# beefocus.net
KiCad netlist of a schematic drawn in EAGLE
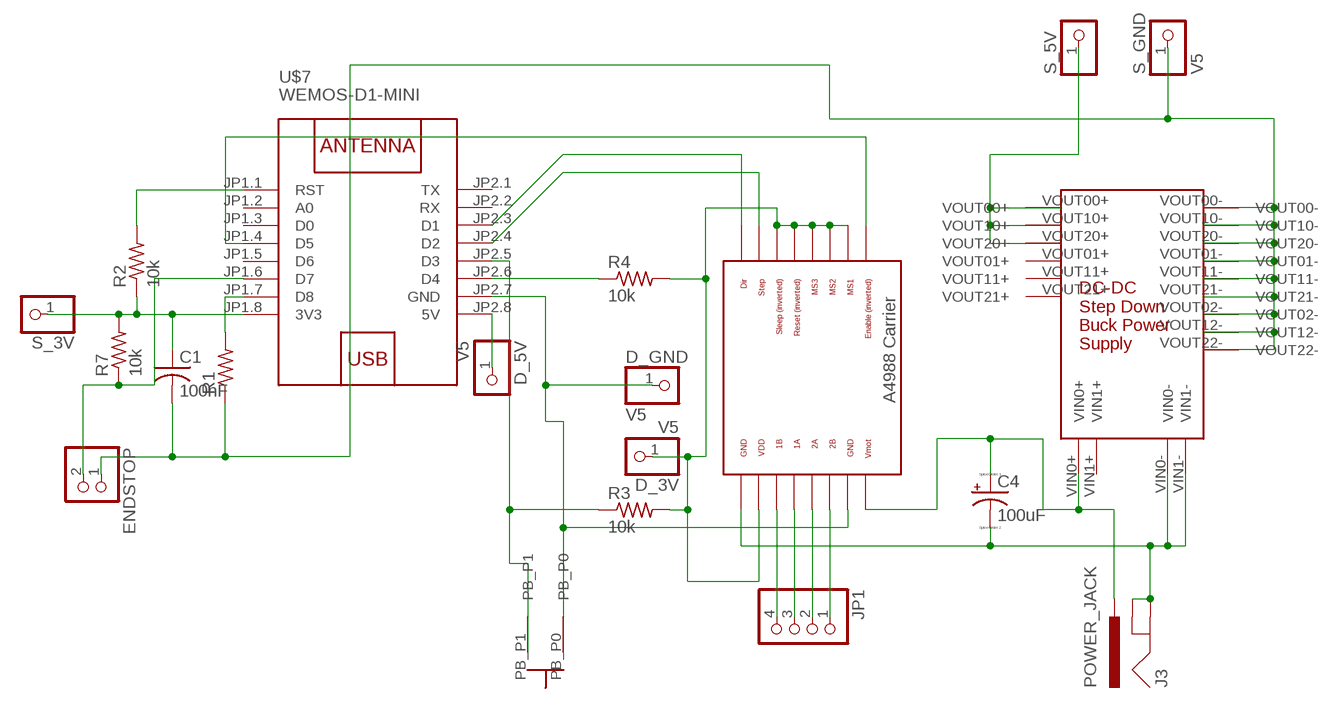
[diagram p0: schematic, sheet 1]

(export (version "E")
  (design (tool "Eeschema 10.0.6"))
  (components
    (comp (ref "C1")
      (value "100nF")
      (footprint "eagle-import:C050-024X044")
      (libsource (lib "eagle-import") (part "C-US050-024X044"))
    )
    (comp (ref "C4")
      (value "100uF")
      (footprint "eagle-import:E3,5-8")
      (libsource (lib "eagle-import") (part "CPOL-USE3.5-8"))
    )
    (comp (ref "D_3V")
      (value "V5")
      (footprint "eagle-import:1X01")
      (libsource (lib "eagle-import") (part "PINHD-1X1"))
    )
    (comp (ref "D_5V")
      (value "V5")
      (footprint "eagle-import:1X01")
      (libsource (lib "eagle-import") (part "PINHD-1X1"))
    )
    (comp (ref "D_GND")
      (value "V5")
      (footprint "eagle-import:1X01")
      (libsource (lib "eagle-import") (part "PINHD-1X1"))
    )
    (comp (ref "ENDSTOP")
      (value "PINHD-1X2/90")
      (footprint "eagle-import:1X02_90")
      (libsource (lib "eagle-import") (part "PINHD-1X2/90"))
    )
    (comp (ref "J3")
      (value "POWER_JACK")
      (footprint "eagle-import:POWER_JACK_PTH")
      (libsource (lib "eagle-import") (part "POWER_JACK"))
    )
    (comp (ref "JP1")
      (value "PINHD-1X4/90")
      (footprint "eagle-import:1X04_90")
      (libsource (lib "eagle-import") (part "PINHD-1X4/90"))
    )
    (comp (ref "R1")
      (value "R-US_0204/7")
      (footprint "eagle-import:0204_7")
      (libsource (lib "eagle-import") (part "R-US_0204/7"))
    )
    (comp (ref "R2")
      (value "10k")
      (footprint "eagle-import:0204_7")
      (libsource (lib "eagle-import") (part "R-US_0204/7"))
    )
    (comp (ref "R3")
      (value "10k")
      (footprint "eagle-import:0309V")
      (libsource (lib "eagle-import") (part "R-US_0309/V"))
    )
    (comp (ref "R4")
      (value "10k")
      (footprint "eagle-import:0204_7")
      (libsource (lib "eagle-import") (part "R-US_0204/7"))
    )
    (comp (ref "R7")
      (value "10k")
      (footprint "eagle-import:0309V")
      (libsource (lib "eagle-import") (part "R-US_0309/V"))
    )
    (comp (ref "S_3V")
      (value "PINHD-1X1")
      (footprint "eagle-import:1X01")
      (libsource (lib "eagle-import") (part "PINHD-1X1"))
    )
    (comp (ref "S_5V")
      (value "PINHD-1X1")
      (footprint "eagle-import:1X01")
      (libsource (lib "eagle-import") (part "PINHD-1X1"))
    )
    (comp (ref "S_GND")
      (value "V5")
      (footprint "eagle-import:1X01")
      (libsource (lib "eagle-import") (part "PINHD-1X1"))
    )
    (comp (ref "U$1")
      (value "POLOLU_A4983CARRIER")
      (footprint "eagle-import:A4988BREAKOUT")
      (libsource (lib "eagle-import") (part "POLOLU_A4983CARRIER"))
    )
    (comp (ref "U$6")
      (value "DCPOWERCONV_R2")
      (footprint "eagle-import:DCPOWERCONV_R2")
      (libsource (lib "eagle-import") (part "DCPOWERCONV_R2"))
    )
    (comp (ref "U$7")
      (value "WEMOS-D1-MINI")
      (footprint "eagle-import:WEMOS-D1-MINI")
      (libsource (lib "eagle-import") (part "WEMOS-D1-MINI"))
    )
    (comp (ref "U$8")
      (value "BUTTON6X6X10MMSIDE")
      (footprint "eagle-import:BUTTON6X6X10MMSIDE")
      (libsource (lib "eagle-import") (part "BUTTON6X6X10MMSIDE"))
    )
  )
  (nets
    (net (code "1") (name "Net-(C1-Pad2)") (class "Default")
      (node (ref "C1") (pin "2") (pinfunction "2_2") (pintype "passive"))
      (node (ref "ENDSTOP") (pin "1") (pinfunction "1_1") (pintype "passive"))
      (node (ref "R1") (pin "1") (pinfunction "1_1") (pintype "passive"))
      (node (ref "S_GND") (pin "1") (pinfunction "1_1") (pintype "passive"))
      (node (ref "U$6") (pin "VOUT00-") (pinfunction "VOUT00-_VOUT00-") (pintype "bidirectional"))
      (node (ref "U$6") (pin "VOUT01-") (pinfunction "VOUT01-_VOUT01-") (pintype "bidirectional"))
      (node (ref "U$6") (pin "VOUT02-") (pinfunction "VOUT02-_VOUT02-") (pintype "bidirectional"))
      (node (ref "U$6") (pin "VOUT10-") (pinfunction "VOUT10-_VOUT10-") (pintype "bidirectional"))
      (node (ref "U$6") (pin "VOUT11-") (pinfunction "VOUT11-_VOUT11-") (pintype "bidirectional"))
      (node (ref "U$6") (pin "VOUT12-") (pinfunction "VOUT12-_VOUT12-") (pintype "bidirectional"))
      (node (ref "U$6") (pin "VOUT20-") (pinfunction "VOUT20-_VOUT20-") (pintype "bidirectional"))
      (node (ref "U$6") (pin "VOUT21-") (pinfunction "VOUT21-_VOUT21-") (pintype "bidirectional"))
      (node (ref "U$6") (pin "VOUT22-") (pinfunction "VOUT22-_VOUT22-") (pintype "bidirectional"))
    )
    (net (code "2") (name "Net-(C4-Pad+)") (class "Default")
      (node (ref "C4") (pin "+") (pinfunction "+_+") (pintype "passive"))
      (node (ref "J3") (pin "PWR") (pinfunction "PWR_PWR") (pintype "bidirectional"))
      (node (ref "U$1") (pin "VMOT") (pinfunction "VMOT_VMOT") (pintype "power_in"))
      (node (ref "U$6") (pin "VIN0+") (pinfunction "VIN0+_VIN0+") (pintype "bidirectional"))
    )
    (net (code "3") (name "Net-(C4-Pad-)") (class "Default")
      (node (ref "C4") (pin "-") (pinfunction "-_-") (pintype "passive"))
      (node (ref "J3") (pin "GND") (pinfunction "GND_GND") (pintype "bidirectional"))
      (node (ref "J3") (pin "GNDBREAK") (pinfunction "GNDBREAK_GNDBREAK") (pintype "bidirectional"))
      (node (ref "U$1") (pin "GND@0") (pinfunction "GND_GND@0") (pintype "power_in"))
      (node (ref "U$6") (pin "VIN0-") (pinfunction "VIN0-_VIN0-") (pintype "bidirectional"))
      (node (ref "U$6") (pin "VIN1-") (pinfunction "VIN1-_VIN1-") (pintype "bidirectional"))
    )
    (net (code "4") (name "Net-(JP1-Pad1)") (class "Default")
      (node (ref "JP1") (pin "1") (pinfunction "1_1") (pintype "passive"))
      (node (ref "U$1") (pin "2B") (pinfunction "2B_2B") (pintype "output"))
    )
    (net (code "5") (name "Net-(JP1-Pad2)") (class "Default")
      (node (ref "JP1") (pin "2") (pinfunction "2_2") (pintype "passive"))
      (node (ref "U$1") (pin "2A") (pinfunction "2A_2A") (pintype "output"))
    )
    (net (code "6") (name "Net-(JP1-Pad3)") (class "Default")
      (node (ref "JP1") (pin "3") (pinfunction "3_3") (pintype "passive"))
      (node (ref "U$1") (pin "1A") (pinfunction "1A_1A") (pintype "output"))
    )
    (net (code "7") (name "Net-(JP1-Pad4)") (class "Default")
      (node (ref "JP1") (pin "4") (pinfunction "4_4") (pintype "passive"))
      (node (ref "U$1") (pin "1B") (pinfunction "1B_1B") (pintype "output"))
    )
    (net (code "8") (name "Net-(S_5V-Pad1)") (class "Default")
      (node (ref "S_5V") (pin "1") (pinfunction "1_1") (pintype "passive"))
      (node (ref "U$6") (pin "VOUT00+") (pinfunction "VOUT00+_VOUT00+") (pintype "bidirectional"))
      (node (ref "U$6") (pin "VOUT10+") (pinfunction "VOUT10+_VOUT10+") (pintype "bidirectional"))
      (node (ref "U$6") (pin "VOUT20+") (pinfunction "VOUT20+_VOUT20+") (pintype "bidirectional"))
    )
    (net (code "9") (name "Net-(U$1-SLEEP)") (class "Default")
      (node (ref "D_3V") (pin "1") (pinfunction "1_1") (pintype "passive"))
      (node (ref "R3") (pin "2") (pinfunction "2_2") (pintype "passive"))
      (node (ref "R4") (pin "2") (pinfunction "2_2") (pintype "passive"))
      (node (ref "U$1") (pin "MS1") (pinfunction "MS1_MS1") (pintype "input"))
      (node (ref "U$1") (pin "MS2") (pinfunction "MS2_MS2") (pintype "input"))
      (node (ref "U$1") (pin "MS3") (pinfunction "MS3_MS3") (pintype "input"))
      (node (ref "U$1") (pin "RST") (pinfunction "RST_RST") (pintype "input"))
      (node (ref "U$1") (pin "SLP") (pinfunction "SLEEP_SLP") (pintype "input"))
      (node (ref "U$1") (pin "VDD") (pinfunction "VDD_VDD") (pintype "power_in"))
    )
    (net (code "10") (name "Net-(U$7-3V3)") (class "Default")
      (node (ref "C1") (pin "1") (pinfunction "1_1") (pintype "passive"))
      (node (ref "R2") (pin "1") (pinfunction "1_1") (pintype "passive"))
      (node (ref "R7") (pin "2") (pinfunction "2_2") (pintype "passive"))
      (node (ref "S_3V") (pin "1") (pinfunction "1_1") (pintype "passive"))
      (node (ref "U$7") (pin "JP1.8") (pinfunction "3V3_JP1.8") (pintype "power_in"))
    )
    (net (code "11") (name "Net-(U$7-5V)") (class "Default")
      (node (ref "D_5V") (pin "1") (pinfunction "1_1") (pintype "passive"))
      (node (ref "U$7") (pin "JP2.8") (pinfunction "5V_JP2.8") (pintype "power_in"))
    )
    (net (code "12") (name "Net-(U$7-D1)") (class "Default")
      (node (ref "U$1") (pin "DIR") (pinfunction "DIR_DIR") (pintype "input"))
      (node (ref "U$7") (pin "JP2.3") (pinfunction "D1_JP2.3") (pintype "bidirectional"))
    )
    (net (code "13") (name "Net-(U$7-D2)") (class "Default")
      (node (ref "U$1") (pin "STEP") (pinfunction "STEP_STEP") (pintype "input"))
      (node (ref "U$7") (pin "JP2.4") (pinfunction "D2_JP2.4") (pintype "bidirectional"))
    )
    (net (code "14") (name "Net-(U$7-D3)") (class "Default")
      (node (ref "R3") (pin "1") (pinfunction "1_1") (pintype "passive"))
      (node (ref "U$7") (pin "JP2.5") (pinfunction "D3_JP2.5") (pintype "bidirectional"))
      (node (ref "U$8") (pin "PB_P1") (pinfunction "PB_P1_PB_P1") (pintype "bidirectional"))
    )
    (net (code "15") (name "Net-(U$7-D4)") (class "Default")
      (node (ref "R4") (pin "1") (pinfunction "1_1") (pintype "passive"))
      (node (ref "U$7") (pin "JP2.6") (pinfunction "D4_JP2.6") (pintype "bidirectional"))
    )
    (net (code "16") (name "Net-(U$7-D5)") (class "Default")
      (node (ref "U$1") (pin "EN") (pinfunction "EN_EN") (pintype "input"))
      (node (ref "U$7") (pin "JP1.4") (pinfunction "D5_JP1.4") (pintype "bidirectional"))
    )
    (net (code "17") (name "Net-(U$7-D7)") (class "Default")
      (node (ref "ENDSTOP") (pin "2") (pinfunction "2_2") (pintype "passive"))
      (node (ref "R7") (pin "1") (pinfunction "1_1") (pintype "passive"))
      (node (ref "U$7") (pin "JP1.6") (pinfunction "D7_JP1.6") (pintype "bidirectional"))
    )
    (net (code "18") (name "Net-(U$7-D8)") (class "Default")
      (node (ref "R1") (pin "2") (pinfunction "2_2") (pintype "passive"))
      (node (ref "U$7") (pin "JP1.7") (pinfunction "D8_JP1.7") (pintype "bidirectional"))
    )
    (net (code "19") (name "Net-(U$7-GND)") (class "Default")
      (node (ref "D_GND") (pin "1") (pinfunction "1_1") (pintype "passive"))
      (node (ref "U$1") (pin "GND") (pinfunction "GND_GND") (pintype "power_in"))
      (node (ref "U$7") (pin "JP2.7") (pinfunction "GND_JP2.7") (pintype "power_in"))
      (node (ref "U$8") (pin "PB_P0") (pinfunction "PB_P0_PB_P0") (pintype "bidirectional"))
    )
    (net (code "20") (name "Net-(U$7-RST)") (class "Default")
      (node (ref "R2") (pin "2") (pinfunction "2_2") (pintype "passive"))
      (node (ref "U$7") (pin "JP1.1") (pinfunction "RST_JP1.1") (pintype "bidirectional"))
    )
    (net (code "21") (name "unconnected-(U$6-PadVIN1+)") (class "Default")
      (node (ref "U$6") (pin "VIN1+") (pinfunction "VIN1+_VIN1+") (pintype "bidirectional"))
    )
    (net (code "22") (name "unconnected-(U$6-PadVOUT01+)") (class "Default")
      (node (ref "U$6") (pin "VOUT01+") (pinfunction "VOUT01+_VOUT01+") (pintype "bidirectional"))
    )
    (net (code "23") (name "unconnected-(U$6-PadVOUT11+)") (class "Default")
      (node (ref "U$6") (pin "VOUT11+") (pinfunction "VOUT11+_VOUT11+") (pintype "bidirectional"))
    )
    (net (code "24") (name "unconnected-(U$6-PadVOUT21+)") (class "Default")
      (node (ref "U$6") (pin "VOUT21+") (pinfunction "VOUT21+_VOUT21+") (pintype "bidirectional"))
    )
    (net (code "25") (name "unconnected-(U$7-A0-PadJP1.2)") (class "Default")
      (node (ref "U$7") (pin "JP1.2") (pinfunction "A0_JP1.2") (pintype "bidirectional"))
    )
    (net (code "26") (name "unconnected-(U$7-D0-PadJP1.3)") (class "Default")
      (node (ref "U$7") (pin "JP1.3") (pinfunction "D0_JP1.3") (pintype "bidirectional"))
    )
    (net (code "27") (name "unconnected-(U$7-D6-PadJP1.5)") (class "Default")
      (node (ref "U$7") (pin "JP1.5") (pinfunction "D6_JP1.5") (pintype "bidirectional"))
    )
    (net (code "28") (name "unconnected-(U$7-RX-PadJP2.2)") (class "Default")
      (node (ref "U$7") (pin "JP2.2") (pinfunction "RX_JP2.2") (pintype "bidirectional"))
    )
    (net (code "29") (name "unconnected-(U$7-TX-PadJP2.1)") (class "Default")
      (node (ref "U$7") (pin "JP2.1") (pinfunction "TX_JP2.1") (pintype "bidirectional"))
    )
  )
)
